# Relay_Logic.net
KiCad netlist of a schematic drawn in Altium Designer
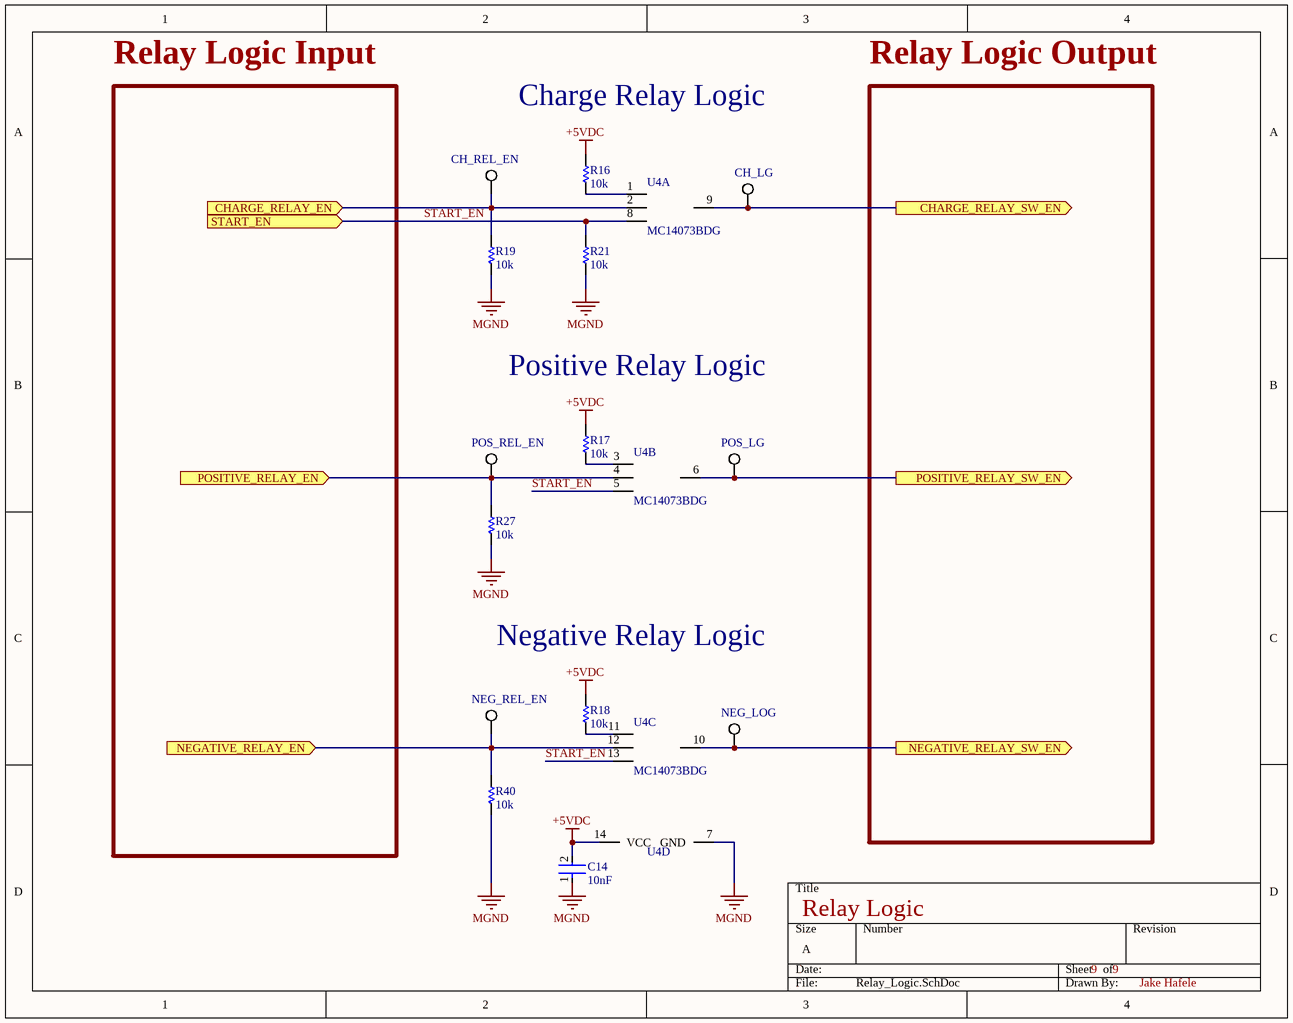
[diagram p0: Relay_Logic.SchDoc]

(export (version "E")
  (design (tool "Eeschema 10.0.6"))
  (components
    (comp (ref "C14")
      (value "CGA3E2X8R2A103K080AD")
      (footprint "FP-CGA3E-0_3-0_1-IPC_A")
      (description "Cap Ceramic 10nF 100V X8R 10% Pad SMD 0603 +150°C Automotive T/R")
      (fields (field (name "CAPACITANCE") "10nF") (field (name "TOLERANCE") "10%"))
      (libsource (lib "Altium Content Vault") (part "b4654b650e69147ec39a6b967a45e02"))
    )
    (comp (ref "CH_LG")
      (value "Test Point")
      (footprint "Test Point")
      (libsource (lib "BPS") (part "Test Point"))
    )
    (comp (ref "CH_REL_EN")
      (value "Test Point")
      (footprint "Test Point")
      (libsource (lib "BPS") (part "Test Point"))
    )
    (comp (ref "NEG_LOG")
      (value "Test Point")
      (footprint "Test Point")
      (libsource (lib "BPS") (part "Test Point"))
    )
    (comp (ref "NEG_REL_EN")
      (value "Test Point")
      (footprint "Test Point")
      (libsource (lib "BPS") (part "Test Point"))
    )
    (comp (ref "POS_LG")
      (value "Test Point")
      (footprint "Test Point")
      (libsource (lib "BPS") (part "Test Point"))
    )
    (comp (ref "POS_REL_EN")
      (value "Test Point")
      (footprint "Test Point")
      (libsource (lib "BPS") (part "Test Point"))
    )
    (comp (ref "R16")
      (value "RES_10k_1%_0603")
      (footprint "R_0603")
      (fields
        (field (name "MANUFACTURER PART NUMBER") "RC0603FR-0710KL")
        (field (name "MANUFACTURER") "Yageo")
        (field (name "DIGIKEY PART NUMBER") "311-10.0KHRCT-ND")
        (field (name "SCHEMATICINFORMATION") "10k")
      )
      (libsource (lib "Resistors") (part "RES_10k_1%_0603"))
    )
    (comp (ref "R17")
      (value "RES_10k_1%_0603")
      (footprint "R_0603")
      (fields
        (field (name "MANUFACTURER PART NUMBER") "RC0603FR-0710KL")
        (field (name "MANUFACTURER") "Yageo")
        (field (name "DIGIKEY PART NUMBER") "311-10.0KHRCT-ND")
        (field (name "SCHEMATICINFORMATION") "10k")
      )
      (libsource (lib "Resistors") (part "RES_10k_1%_0603"))
    )
    (comp (ref "R18")
      (value "RES_10k_1%_0603")
      (footprint "R_0603")
      (fields
        (field (name "MANUFACTURER PART NUMBER") "RC0603FR-0710KL")
        (field (name "MANUFACTURER") "Yageo")
        (field (name "DIGIKEY PART NUMBER") "311-10.0KHRCT-ND")
        (field (name "SCHEMATICINFORMATION") "10k")
      )
      (libsource (lib "Resistors") (part "RES_10k_1%_0603"))
    )
    (comp (ref "R19")
      (value "RES_10k_1%_0603")
      (footprint "R_0603")
      (fields
        (field (name "MANUFACTURER PART NUMBER") "RC0603FR-0710KL")
        (field (name "MANUFACTURER") "Yageo")
        (field (name "DIGIKEY PART NUMBER") "311-10.0KHRCT-ND")
        (field (name "SCHEMATICINFORMATION") "10k")
      )
      (libsource (lib "Resistors") (part "RES_10k_1%_0603"))
    )
    (comp (ref "R21")
      (value "RES_10k_1%_0603")
      (footprint "R_0603")
      (fields
        (field (name "MANUFACTURER PART NUMBER") "RC0603FR-0710KL")
        (field (name "MANUFACTURER") "Yageo")
        (field (name "DIGIKEY PART NUMBER") "311-10.0KHRCT-ND")
        (field (name "SCHEMATICINFORMATION") "10k")
      )
      (libsource (lib "Resistors") (part "RES_10k_1%_0603"))
    )
    (comp (ref "R27")
      (value "RES_10k_1%_0603")
      (footprint "R_0603")
      (fields
        (field (name "MANUFACTURER PART NUMBER") "RC0603FR-0710KL")
        (field (name "MANUFACTURER") "Yageo")
        (field (name "DIGIKEY PART NUMBER") "311-10.0KHRCT-ND")
        (field (name "SCHEMATICINFORMATION") "10k")
      )
      (libsource (lib "Resistors") (part "RES_10k_1%_0603"))
    )
    (comp (ref "R40")
      (value "RES_10k_1%_0603")
      (footprint "R_0603")
      (fields
        (field (name "MANUFACTURER PART NUMBER") "RC0603FR-0710KL")
        (field (name "MANUFACTURER") "Yageo")
        (field (name "DIGIKEY PART NUMBER") "311-10.0KHRCT-ND")
        (field (name "SCHEMATICINFORMATION") "10k")
      )
      (libsource (lib "Resistors") (part "RES_10k_1%_0603"))
    )
    (comp (ref "U4")
      (value "MC14073BDG")
      (footprint "SO14")
      (description "Triple 3-Input AND")
      (fields (field (name "DRAWN BY") "Aaron Mills"))
      (libsource (lib "BPSHeadNode") (part "MC14073BDG"))
    )
  )
  (nets
    (net (code "1") (name "+5VDC") (class "Default")
      (node (ref "C14") (pin "2") (pinfunction "2_2") (pintype "passive"))
      (node (ref "R16") (pin "1") (pinfunction "1_1") (pintype "passive"))
      (node (ref "R17") (pin "1") (pinfunction "1_1") (pintype "passive"))
      (node (ref "R18") (pin "1") (pinfunction "1_1") (pintype "passive"))
      (node (ref "U4") (pin "14") (pinfunction "VCC_14") (pintype "passive"))
    )
    (net (code "2") (name "/CHARGE_RELAY_EN") (class "Default")
      (node (ref "CH_REL_EN") (pin "1") (pinfunction "1_1") (pintype "passive"))
      (node (ref "R19") (pin "1") (pinfunction "1_1") (pintype "passive"))
      (node (ref "U4") (pin "2") (pintype "passive"))
    )
    (net (code "3") (name "/CHARGE_RELAY_SW_EN") (class "Default")
      (node (ref "CH_LG") (pin "1") (pinfunction "1_1") (pintype "passive"))
      (node (ref "U4") (pin "9") (pintype "passive"))
    )
    (net (code "4") (name "/NEGATIVE_RELAY_EN") (class "Default")
      (node (ref "NEG_REL_EN") (pin "1") (pinfunction "1_1") (pintype "passive"))
      (node (ref "R40") (pin "1") (pinfunction "1_1") (pintype "passive"))
      (node (ref "U4") (pin "12") (pintype "passive"))
    )
    (net (code "5") (name "/NEGATIVE_RELAY_SW_EN") (class "Default")
      (node (ref "NEG_LOG") (pin "1") (pinfunction "1_1") (pintype "passive"))
      (node (ref "U4") (pin "10") (pintype "passive"))
    )
    (net (code "6") (name "/POSITIVE_RELAY_EN") (class "Default")
      (node (ref "POS_REL_EN") (pin "1") (pinfunction "1_1") (pintype "passive"))
      (node (ref "R27") (pin "1") (pinfunction "1_1") (pintype "passive"))
      (node (ref "U4") (pin "4") (pintype "passive"))
    )
    (net (code "7") (name "/POSITIVE_RELAY_SW_EN") (class "Default")
      (node (ref "POS_LG") (pin "1") (pinfunction "1_1") (pintype "passive"))
      (node (ref "U4") (pin "6") (pintype "passive"))
    )
    (net (code "8") (name "/START_EN") (class "Default")
      (node (ref "R21") (pin "1") (pinfunction "1_1") (pintype "passive"))
      (node (ref "U4") (pin "13") (pintype "passive"))
      (node (ref "U4") (pin "5") (pintype "passive"))
      (node (ref "U4") (pin "8") (pintype "passive"))
    )
    (net (code "9") (name "MGND") (class "Default")
      (node (ref "C14") (pin "1") (pinfunction "1_1") (pintype "passive"))
      (node (ref "R19") (pin "2") (pinfunction "2_2") (pintype "passive"))
      (node (ref "R21") (pin "2") (pinfunction "2_2") (pintype "passive"))
      (node (ref "R27") (pin "2") (pinfunction "2_2") (pintype "passive"))
      (node (ref "R40") (pin "2") (pinfunction "2_2") (pintype "passive"))
      (node (ref "U4") (pin "7") (pinfunction "GND_7") (pintype "passive"))
    )
    (net (code "10") (name "Net-(R16-Pad2)") (class "Default")
      (node (ref "R16") (pin "2") (pinfunction "2_2") (pintype "passive"))
      (node (ref "U4") (pin "1") (pintype "passive"))
    )
    (net (code "11") (name "Net-(R17-Pad2)") (class "Default")
      (node (ref "R17") (pin "2") (pinfunction "2_2") (pintype "passive"))
      (node (ref "U4") (pin "3") (pintype "passive"))
    )
    (net (code "12") (name "Net-(R18-Pad2)") (class "Default")
      (node (ref "R18") (pin "2") (pinfunction "2_2") (pintype "passive"))
      (node (ref "U4") (pin "11") (pintype "passive"))
    )
  )
)
